# elysium_v0_7.net
KiCad netlist of a schematic drawn in EAGLE
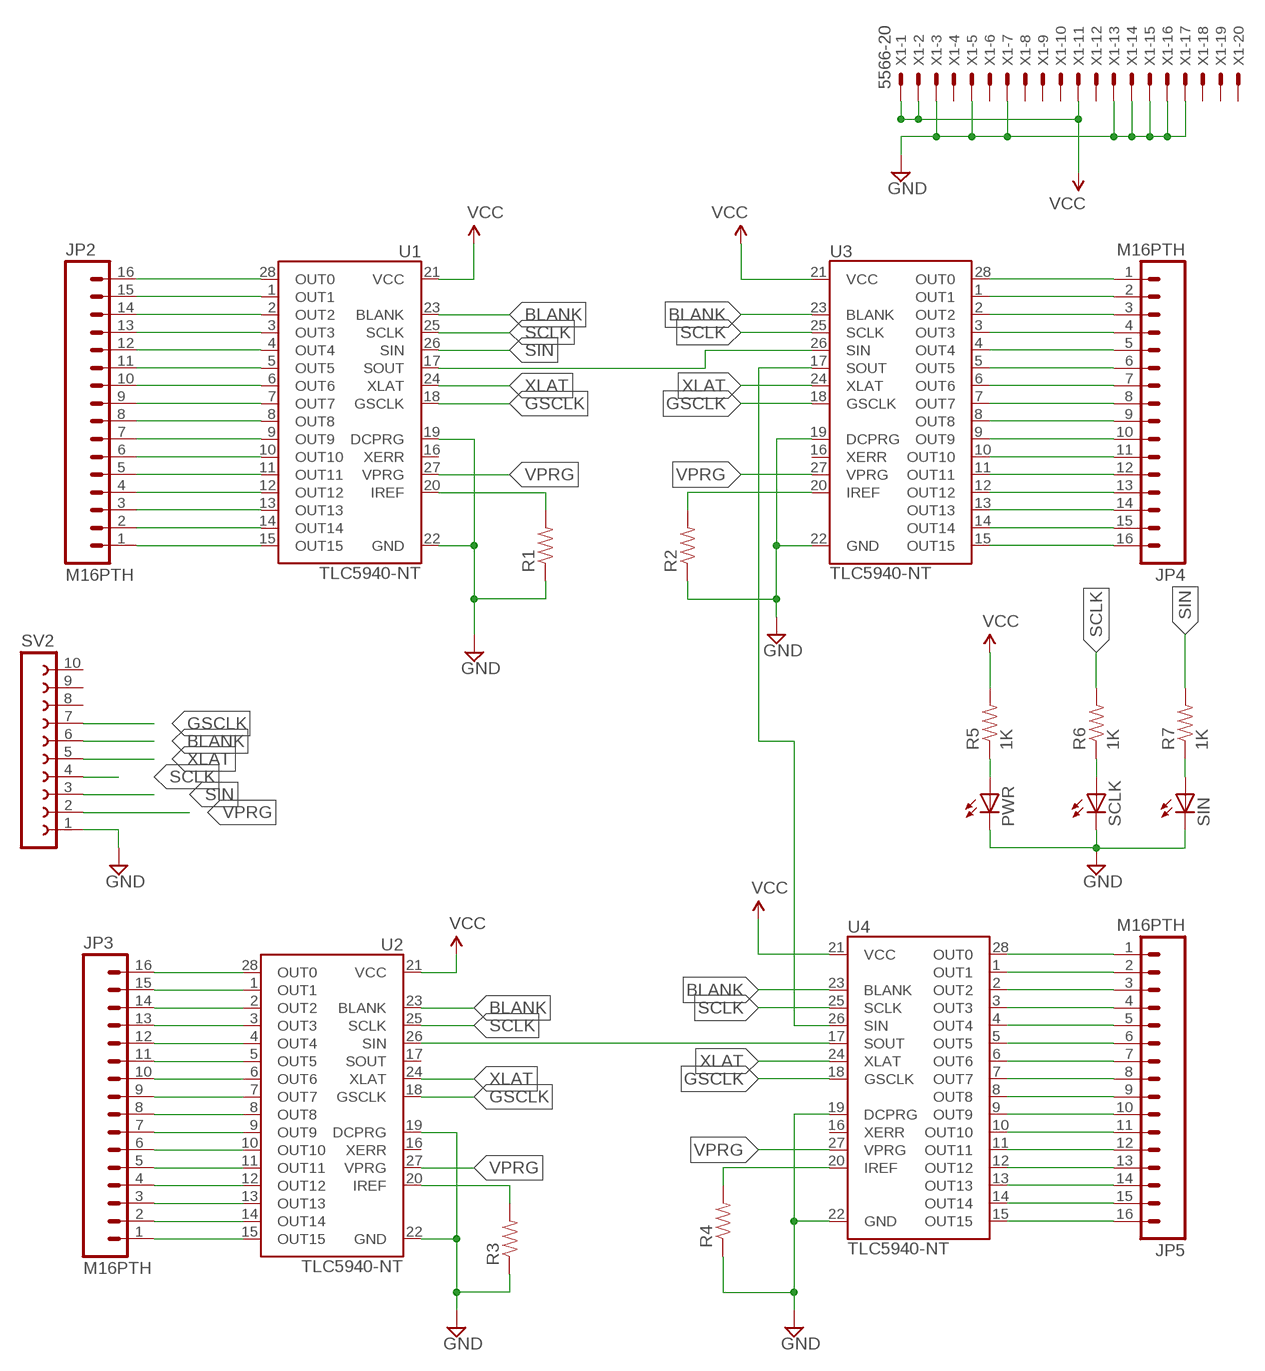
[diagram p0: schematic, sheet 1]

(export (version "E")
  (design (tool "Eeschema 10.0.6"))
  (components
    (comp (ref "JP2")
      (value "M16PTH")
      (footprint "eagle-import:1X16")
      (libsource (lib "eagle-import") (part "M16PTH"))
    )
    (comp (ref "JP3")
      (value "M16PTH")
      (footprint "eagle-import:1X16")
      (libsource (lib "eagle-import") (part "M16PTH"))
    )
    (comp (ref "JP4")
      (value "M16PTH")
      (footprint "eagle-import:1X16")
      (libsource (lib "eagle-import") (part "M16PTH"))
    )
    (comp (ref "JP5")
      (value "M16PTH")
      (footprint "eagle-import:1X16")
      (libsource (lib "eagle-import") (part "M16PTH"))
    )
    (comp (ref "PWR")
      (value "LED5MM")
      (footprint "eagle-import:LED5MM")
      (libsource (lib "eagle-import") (part "LED5MM"))
    )
    (comp (ref "R1")
      (value "RESISTOREZ")
      (footprint "eagle-import:AXIAL-0.3EZ")
      (libsource (lib "eagle-import") (part "RESISTOREZ"))
    )
    (comp (ref "R2")
      (value "RESISTOREZ")
      (footprint "eagle-import:AXIAL-0.3EZ")
      (libsource (lib "eagle-import") (part "RESISTOREZ"))
    )
    (comp (ref "R3")
      (value "RESISTOREZ")
      (footprint "eagle-import:AXIAL-0.3EZ")
      (libsource (lib "eagle-import") (part "RESISTOREZ"))
    )
    (comp (ref "R4")
      (value "RESISTOREZ")
      (footprint "eagle-import:AXIAL-0.3EZ")
      (libsource (lib "eagle-import") (part "RESISTOREZ"))
    )
    (comp (ref "R5")
      (value "1K")
      (footprint "eagle-import:AXIAL-0.3EZ")
      (libsource (lib "eagle-import") (part "RESISTOREZ"))
    )
    (comp (ref "R6")
      (value "1K")
      (footprint "eagle-import:AXIAL-0.3EZ")
      (libsource (lib "eagle-import") (part "RESISTOREZ"))
    )
    (comp (ref "R7")
      (value "1K")
      (footprint "eagle-import:AXIAL-0.3EZ")
      (libsource (lib "eagle-import") (part "RESISTOREZ"))
    )
    (comp (ref "SCLK")
      (value "LED5MM")
      (footprint "eagle-import:LED5MM")
      (libsource (lib "eagle-import") (part "LED5MM"))
    )
    (comp (ref "SIN")
      (value "LED5MM")
      (footprint "eagle-import:LED5MM")
      (libsource (lib "eagle-import") (part "LED5MM"))
    )
    (comp (ref "SV2")
      (value "FE10-1")
      (footprint "eagle-import:FE10")
      (libsource (lib "eagle-import") (part "FE10-1"))
    )
    (comp (ref "U1")
      (value "TLC5940-NT")
      (footprint "eagle-import:DIL28-3")
      (libsource (lib "eagle-import") (part "TLC5940-NT"))
    )
    (comp (ref "U2")
      (value "TLC5940-NT")
      (footprint "eagle-import:DIL28-3")
      (libsource (lib "eagle-import") (part "TLC5940-NT"))
    )
    (comp (ref "U3")
      (value "TLC5940-NT")
      (footprint "eagle-import:DIL28-3")
      (libsource (lib "eagle-import") (part "TLC5940-NT"))
    )
    (comp (ref "U4")
      (value "TLC5940-NT")
      (footprint "eagle-import:DIL28-3")
      (libsource (lib "eagle-import") (part "TLC5940-NT"))
    )
    (comp (ref "X1")
      (value "5566-20")
      (footprint "eagle-import:5566-20")
      (libsource (lib "eagle-import") (part "5566-20"))
    )
  )
  (nets
    (net (code "1") (name "BLANK") (class "Default")
      (node (ref "SV2") (pin "6") (pinfunction "6_6") (pintype "passive"))
      (node (ref "U1") (pin "23") (pinfunction "BLANK_23") (pintype "bidirectional"))
      (node (ref "U2") (pin "23") (pinfunction "BLANK_23") (pintype "bidirectional"))
      (node (ref "U3") (pin "23") (pinfunction "BLANK_23") (pintype "bidirectional"))
      (node (ref "U4") (pin "23") (pinfunction "BLANK_23") (pintype "bidirectional"))
    )
    (net (code "2") (name "GND") (class "Default")
      (node (ref "PWR") (pin "K") (pinfunction "C_K") (pintype "passive"))
      (node (ref "R1") (pin "P$1") (pinfunction "1_P$1") (pintype "passive"))
      (node (ref "R2") (pin "P$1") (pinfunction "1_P$1") (pintype "passive"))
      (node (ref "R3") (pin "P$1") (pinfunction "1_P$1") (pintype "passive"))
      (node (ref "R4") (pin "P$1") (pinfunction "1_P$1") (pintype "passive"))
      (node (ref "SCLK") (pin "K") (pinfunction "C_K") (pintype "passive"))
      (node (ref "SIN") (pin "K") (pinfunction "C_K") (pintype "passive"))
      (node (ref "SV2") (pin "1") (pinfunction "1_1") (pintype "passive"))
      (node (ref "U1") (pin "19") (pinfunction "DCPRG_19") (pintype "bidirectional"))
      (node (ref "U1") (pin "22") (pinfunction "GND_22") (pintype "bidirectional"))
      (node (ref "U2") (pin "19") (pinfunction "DCPRG_19") (pintype "bidirectional"))
      (node (ref "U2") (pin "22") (pinfunction "GND_22") (pintype "bidirectional"))
      (node (ref "U3") (pin "19") (pinfunction "DCPRG_19") (pintype "bidirectional"))
      (node (ref "U3") (pin "22") (pinfunction "GND_22") (pintype "bidirectional"))
      (node (ref "U4") (pin "19") (pinfunction "DCPRG_19") (pintype "bidirectional"))
      (node (ref "U4") (pin "22") (pinfunction "GND_22") (pintype "bidirectional"))
      (node (ref "X1") (pin "13") (pinfunction "S_13") (pintype "passive"))
      (node (ref "X1") (pin "14") (pinfunction "S_14") (pintype "passive"))
      (node (ref "X1") (pin "15") (pinfunction "S_15") (pintype "passive"))
      (node (ref "X1") (pin "16") (pinfunction "S_16") (pintype "passive"))
      (node (ref "X1") (pin "17") (pinfunction "S_17") (pintype "passive"))
      (node (ref "X1") (pin "3") (pinfunction "S_3") (pintype "passive"))
      (node (ref "X1") (pin "5") (pinfunction "S_5") (pintype "passive"))
      (node (ref "X1") (pin "7") (pinfunction "S_7") (pintype "passive"))
    )
    (net (code "3") (name "GSCLK") (class "Default")
      (node (ref "SV2") (pin "7") (pinfunction "7_7") (pintype "passive"))
      (node (ref "U1") (pin "18") (pinfunction "GSCLK_18") (pintype "bidirectional"))
      (node (ref "U2") (pin "18") (pinfunction "GSCLK_18") (pintype "bidirectional"))
      (node (ref "U3") (pin "18") (pinfunction "GSCLK_18") (pintype "bidirectional"))
      (node (ref "U4") (pin "18") (pinfunction "GSCLK_18") (pintype "bidirectional"))
    )
    (net (code "4") (name "Net-(R1-2)") (class "Default")
      (node (ref "R1") (pin "P$2") (pinfunction "2_P$2") (pintype "passive"))
      (node (ref "U1") (pin "20") (pinfunction "IREF_20") (pintype "bidirectional"))
    )
    (net (code "5") (name "Net-(R2-2)") (class "Default")
      (node (ref "R2") (pin "P$2") (pinfunction "2_P$2") (pintype "passive"))
      (node (ref "U3") (pin "20") (pinfunction "IREF_20") (pintype "bidirectional"))
    )
    (net (code "6") (name "Net-(R3-2)") (class "Default")
      (node (ref "R3") (pin "P$2") (pinfunction "2_P$2") (pintype "passive"))
      (node (ref "U2") (pin "20") (pinfunction "IREF_20") (pintype "bidirectional"))
    )
    (net (code "7") (name "Net-(R4-2)") (class "Default")
      (node (ref "R4") (pin "P$2") (pinfunction "2_P$2") (pintype "passive"))
      (node (ref "U4") (pin "20") (pinfunction "IREF_20") (pintype "bidirectional"))
    )
    (net (code "8") (name "Net-(R5-1)") (class "Default")
      (node (ref "PWR") (pin "A") (pinfunction "A_A") (pintype "passive"))
      (node (ref "R5") (pin "P$1") (pinfunction "1_P$1") (pintype "passive"))
    )
    (net (code "9") (name "Net-(R6-1)") (class "Default")
      (node (ref "R6") (pin "P$1") (pinfunction "1_P$1") (pintype "passive"))
      (node (ref "SCLK") (pin "A") (pinfunction "A_A") (pintype "passive"))
    )
    (net (code "10") (name "Net-(R7-1)") (class "Default")
      (node (ref "R7") (pin "P$1") (pinfunction "1_P$1") (pintype "passive"))
      (node (ref "SIN") (pin "A") (pinfunction "A_A") (pintype "passive"))
    )
    (net (code "11") (name "Net-(U1-OUT0)") (class "Default")
      (node (ref "JP2") (pin "16") (pinfunction "16_16") (pintype "passive"))
      (node (ref "U1") (pin "28") (pinfunction "OUT0_28") (pintype "bidirectional"))
    )
    (net (code "12") (name "Net-(U1-OUT1)") (class "Default")
      (node (ref "JP2") (pin "15") (pinfunction "15_15") (pintype "passive"))
      (node (ref "U1") (pin "1") (pinfunction "OUT1_1") (pintype "bidirectional"))
    )
    (net (code "13") (name "Net-(U1-OUT2)") (class "Default")
      (node (ref "JP2") (pin "14") (pinfunction "14_14") (pintype "passive"))
      (node (ref "U1") (pin "2") (pinfunction "OUT2_2") (pintype "bidirectional"))
    )
    (net (code "14") (name "Net-(U1-OUT3)") (class "Default")
      (node (ref "JP2") (pin "13") (pinfunction "13_13") (pintype "passive"))
      (node (ref "U1") (pin "3") (pinfunction "OUT3_3") (pintype "bidirectional"))
    )
    (net (code "15") (name "Net-(U1-OUT4)") (class "Default")
      (node (ref "JP2") (pin "12") (pinfunction "12_12") (pintype "passive"))
      (node (ref "U1") (pin "4") (pinfunction "OUT4_4") (pintype "bidirectional"))
    )
    (net (code "16") (name "Net-(U1-OUT5)") (class "Default")
      (node (ref "JP2") (pin "11") (pinfunction "11_11") (pintype "passive"))
      (node (ref "U1") (pin "5") (pinfunction "OUT5_5") (pintype "bidirectional"))
    )
    (net (code "17") (name "Net-(U1-OUT6)") (class "Default")
      (node (ref "JP2") (pin "10") (pinfunction "10_10") (pintype "passive"))
      (node (ref "U1") (pin "6") (pinfunction "OUT6_6") (pintype "bidirectional"))
    )
    (net (code "18") (name "Net-(U1-OUT7)") (class "Default")
      (node (ref "JP2") (pin "9") (pinfunction "9_9") (pintype "passive"))
      (node (ref "U1") (pin "7") (pinfunction "OUT7_7") (pintype "bidirectional"))
    )
    (net (code "19") (name "Net-(U1-OUT8)") (class "Default")
      (node (ref "JP2") (pin "8") (pinfunction "8_8") (pintype "passive"))
      (node (ref "U1") (pin "8") (pinfunction "OUT8_8") (pintype "bidirectional"))
    )
    (net (code "20") (name "Net-(U1-OUT9)") (class "Default")
      (node (ref "JP2") (pin "7") (pinfunction "7_7") (pintype "passive"))
      (node (ref "U1") (pin "9") (pinfunction "OUT9_9") (pintype "bidirectional"))
    )
    (net (code "21") (name "Net-(U1-OUT10)") (class "Default")
      (node (ref "JP2") (pin "6") (pinfunction "6_6") (pintype "passive"))
      (node (ref "U1") (pin "10") (pinfunction "OUT10_10") (pintype "bidirectional"))
    )
    (net (code "22") (name "Net-(U1-OUT11)") (class "Default")
      (node (ref "JP2") (pin "5") (pinfunction "5_5") (pintype "passive"))
      (node (ref "U1") (pin "11") (pinfunction "OUT11_11") (pintype "bidirectional"))
    )
    (net (code "23") (name "Net-(U1-OUT12)") (class "Default")
      (node (ref "JP2") (pin "4") (pinfunction "4_4") (pintype "passive"))
      (node (ref "U1") (pin "12") (pinfunction "OUT12_12") (pintype "bidirectional"))
    )
    (net (code "24") (name "Net-(U1-OUT13)") (class "Default")
      (node (ref "JP2") (pin "3") (pinfunction "3_3") (pintype "passive"))
      (node (ref "U1") (pin "13") (pinfunction "OUT13_13") (pintype "bidirectional"))
    )
    (net (code "25") (name "Net-(U1-OUT14)") (class "Default")
      (node (ref "JP2") (pin "2") (pinfunction "2_2") (pintype "passive"))
      (node (ref "U1") (pin "14") (pinfunction "OUT14_14") (pintype "bidirectional"))
    )
    (net (code "26") (name "Net-(U1-OUT15)") (class "Default")
      (node (ref "JP2") (pin "1") (pinfunction "1_1") (pintype "passive"))
      (node (ref "U1") (pin "15") (pinfunction "OUT15_15") (pintype "bidirectional"))
    )
    (net (code "27") (name "Net-(U1-SOUT)") (class "Default")
      (node (ref "U1") (pin "17") (pinfunction "SOUT_17") (pintype "bidirectional"))
      (node (ref "U3") (pin "26") (pinfunction "SIN_26") (pintype "bidirectional"))
    )
    (net (code "28") (name "Net-(U2-OUT0)") (class "Default")
      (node (ref "JP3") (pin "16") (pinfunction "16_16") (pintype "passive"))
      (node (ref "U2") (pin "28") (pinfunction "OUT0_28") (pintype "bidirectional"))
    )
    (net (code "29") (name "Net-(U2-OUT1)") (class "Default")
      (node (ref "JP3") (pin "15") (pinfunction "15_15") (pintype "passive"))
      (node (ref "U2") (pin "1") (pinfunction "OUT1_1") (pintype "bidirectional"))
    )
    (net (code "30") (name "Net-(U2-OUT2)") (class "Default")
      (node (ref "JP3") (pin "14") (pinfunction "14_14") (pintype "passive"))
      (node (ref "U2") (pin "2") (pinfunction "OUT2_2") (pintype "bidirectional"))
    )
    (net (code "31") (name "Net-(U2-OUT3)") (class "Default")
      (node (ref "JP3") (pin "13") (pinfunction "13_13") (pintype "passive"))
      (node (ref "U2") (pin "3") (pinfunction "OUT3_3") (pintype "bidirectional"))
    )
    (net (code "32") (name "Net-(U2-OUT4)") (class "Default")
      (node (ref "JP3") (pin "12") (pinfunction "12_12") (pintype "passive"))
      (node (ref "U2") (pin "4") (pinfunction "OUT4_4") (pintype "bidirectional"))
    )
    (net (code "33") (name "Net-(U2-OUT5)") (class "Default")
      (node (ref "JP3") (pin "11") (pinfunction "11_11") (pintype "passive"))
      (node (ref "U2") (pin "5") (pinfunction "OUT5_5") (pintype "bidirectional"))
    )
    (net (code "34") (name "Net-(U2-OUT6)") (class "Default")
      (node (ref "JP3") (pin "10") (pinfunction "10_10") (pintype "passive"))
      (node (ref "U2") (pin "6") (pinfunction "OUT6_6") (pintype "bidirectional"))
    )
    (net (code "35") (name "Net-(U2-OUT7)") (class "Default")
      (node (ref "JP3") (pin "9") (pinfunction "9_9") (pintype "passive"))
      (node (ref "U2") (pin "7") (pinfunction "OUT7_7") (pintype "bidirectional"))
    )
    (net (code "36") (name "Net-(U2-OUT8)") (class "Default")
      (node (ref "JP3") (pin "8") (pinfunction "8_8") (pintype "passive"))
      (node (ref "U2") (pin "8") (pinfunction "OUT8_8") (pintype "bidirectional"))
    )
    (net (code "37") (name "Net-(U2-OUT9)") (class "Default")
      (node (ref "JP3") (pin "7") (pinfunction "7_7") (pintype "passive"))
      (node (ref "U2") (pin "9") (pinfunction "OUT9_9") (pintype "bidirectional"))
    )
    (net (code "38") (name "Net-(U2-OUT10)") (class "Default")
      (node (ref "JP3") (pin "6") (pinfunction "6_6") (pintype "passive"))
      (node (ref "U2") (pin "10") (pinfunction "OUT10_10") (pintype "bidirectional"))
    )
    (net (code "39") (name "Net-(U2-OUT11)") (class "Default")
      (node (ref "JP3") (pin "5") (pinfunction "5_5") (pintype "passive"))
      (node (ref "U2") (pin "11") (pinfunction "OUT11_11") (pintype "bidirectional"))
    )
    (net (code "40") (name "Net-(U2-OUT12)") (class "Default")
      (node (ref "JP3") (pin "4") (pinfunction "4_4") (pintype "passive"))
      (node (ref "U2") (pin "12") (pinfunction "OUT12_12") (pintype "bidirectional"))
    )
    (net (code "41") (name "Net-(U2-OUT13)") (class "Default")
      (node (ref "JP3") (pin "3") (pinfunction "3_3") (pintype "passive"))
      (node (ref "U2") (pin "13") (pinfunction "OUT13_13") (pintype "bidirectional"))
    )
    (net (code "42") (name "Net-(U2-OUT14)") (class "Default")
      (node (ref "JP3") (pin "2") (pinfunction "2_2") (pintype "passive"))
      (node (ref "U2") (pin "14") (pinfunction "OUT14_14") (pintype "bidirectional"))
    )
    (net (code "43") (name "Net-(U2-OUT15)") (class "Default")
      (node (ref "JP3") (pin "1") (pinfunction "1_1") (pintype "passive"))
      (node (ref "U2") (pin "15") (pinfunction "OUT15_15") (pintype "bidirectional"))
    )
    (net (code "44") (name "Net-(U2-SIN)") (class "Default")
      (node (ref "U2") (pin "26") (pinfunction "SIN_26") (pintype "bidirectional"))
      (node (ref "U4") (pin "17") (pinfunction "SOUT_17") (pintype "bidirectional"))
    )
    (net (code "45") (name "Net-(U3-OUT0)") (class "Default")
      (node (ref "JP4") (pin "1") (pinfunction "1_1") (pintype "passive"))
      (node (ref "U3") (pin "28") (pinfunction "OUT0_28") (pintype "bidirectional"))
    )
    (net (code "46") (name "Net-(U3-OUT1)") (class "Default")
      (node (ref "JP4") (pin "2") (pinfunction "2_2") (pintype "passive"))
      (node (ref "U3") (pin "1") (pinfunction "OUT1_1") (pintype "bidirectional"))
    )
    (net (code "47") (name "Net-(U3-OUT2)") (class "Default")
      (node (ref "JP4") (pin "3") (pinfunction "3_3") (pintype "passive"))
      (node (ref "U3") (pin "2") (pinfunction "OUT2_2") (pintype "bidirectional"))
    )
    (net (code "48") (name "Net-(U3-OUT3)") (class "Default")
      (node (ref "JP4") (pin "4") (pinfunction "4_4") (pintype "passive"))
      (node (ref "U3") (pin "3") (pinfunction "OUT3_3") (pintype "bidirectional"))
    )
    (net (code "49") (name "Net-(U3-OUT4)") (class "Default")
      (node (ref "JP4") (pin "5") (pinfunction "5_5") (pintype "passive"))
      (node (ref "U3") (pin "4") (pinfunction "OUT4_4") (pintype "bidirectional"))
    )
    (net (code "50") (name "Net-(U3-OUT5)") (class "Default")
      (node (ref "JP4") (pin "6") (pinfunction "6_6") (pintype "passive"))
      (node (ref "U3") (pin "5") (pinfunction "OUT5_5") (pintype "bidirectional"))
    )
    (net (code "51") (name "Net-(U3-OUT6)") (class "Default")
      (node (ref "JP4") (pin "7") (pinfunction "7_7") (pintype "passive"))
      (node (ref "U3") (pin "6") (pinfunction "OUT6_6") (pintype "bidirectional"))
    )
    (net (code "52") (name "Net-(U3-OUT7)") (class "Default")
      (node (ref "JP4") (pin "8") (pinfunction "8_8") (pintype "passive"))
      (node (ref "U3") (pin "7") (pinfunction "OUT7_7") (pintype "bidirectional"))
    )
    (net (code "53") (name "Net-(U3-OUT8)") (class "Default")
      (node (ref "JP4") (pin "9") (pinfunction "9_9") (pintype "passive"))
      (node (ref "U3") (pin "8") (pinfunction "OUT8_8") (pintype "bidirectional"))
    )
    (net (code "54") (name "Net-(U3-OUT9)") (class "Default")
      (node (ref "JP4") (pin "10") (pinfunction "10_10") (pintype "passive"))
      (node (ref "U3") (pin "9") (pinfunction "OUT9_9") (pintype "bidirectional"))
    )
    (net (code "55") (name "Net-(U3-OUT10)") (class "Default")
      (node (ref "JP4") (pin "11") (pinfunction "11_11") (pintype "passive"))
      (node (ref "U3") (pin "10") (pinfunction "OUT10_10") (pintype "bidirectional"))
    )
    (net (code "56") (name "Net-(U3-OUT11)") (class "Default")
      (node (ref "JP4") (pin "12") (pinfunction "12_12") (pintype "passive"))
      (node (ref "U3") (pin "11") (pinfunction "OUT11_11") (pintype "bidirectional"))
    )
    (net (code "57") (name "Net-(U3-OUT12)") (class "Default")
      (node (ref "JP4") (pin "13") (pinfunction "13_13") (pintype "passive"))
      (node (ref "U3") (pin "12") (pinfunction "OUT12_12") (pintype "bidirectional"))
    )
    (net (code "58") (name "Net-(U3-OUT13)") (class "Default")
      (node (ref "JP4") (pin "14") (pinfunction "14_14") (pintype "passive"))
      (node (ref "U3") (pin "13") (pinfunction "OUT13_13") (pintype "bidirectional"))
    )
    (net (code "59") (name "Net-(U3-OUT14)") (class "Default")
      (node (ref "JP4") (pin "15") (pinfunction "15_15") (pintype "passive"))
      (node (ref "U3") (pin "14") (pinfunction "OUT14_14") (pintype "bidirectional"))
    )
    (net (code "60") (name "Net-(U3-OUT15)") (class "Default")
      (node (ref "JP4") (pin "16") (pinfunction "16_16") (pintype "passive"))
      (node (ref "U3") (pin "15") (pinfunction "OUT15_15") (pintype "bidirectional"))
    )
    (net (code "61") (name "Net-(U3-SOUT)") (class "Default")
      (node (ref "U3") (pin "17") (pinfunction "SOUT_17") (pintype "bidirectional"))
      (node (ref "U4") (pin "26") (pinfunction "SIN_26") (pintype "bidirectional"))
    )
    (net (code "62") (name "Net-(U4-OUT0)") (class "Default")
      (node (ref "JP5") (pin "1") (pinfunction "1_1") (pintype "passive"))
      (node (ref "U4") (pin "28") (pinfunction "OUT0_28") (pintype "bidirectional"))
    )
    (net (code "63") (name "Net-(U4-OUT1)") (class "Default")
      (node (ref "JP5") (pin "2") (pinfunction "2_2") (pintype "passive"))
      (node (ref "U4") (pin "1") (pinfunction "OUT1_1") (pintype "bidirectional"))
    )
    (net (code "64") (name "Net-(U4-OUT2)") (class "Default")
      (node (ref "JP5") (pin "3") (pinfunction "3_3") (pintype "passive"))
      (node (ref "U4") (pin "2") (pinfunction "OUT2_2") (pintype "bidirectional"))
    )
    (net (code "65") (name "Net-(U4-OUT3)") (class "Default")
      (node (ref "JP5") (pin "4") (pinfunction "4_4") (pintype "passive"))
      (node (ref "U4") (pin "3") (pinfunction "OUT3_3") (pintype "bidirectional"))
    )
    (net (code "66") (name "Net-(U4-OUT4)") (class "Default")
      (node (ref "JP5") (pin "5") (pinfunction "5_5") (pintype "passive"))
      (node (ref "U4") (pin "4") (pinfunction "OUT4_4") (pintype "bidirectional"))
    )
    (net (code "67") (name "Net-(U4-OUT5)") (class "Default")
      (node (ref "JP5") (pin "6") (pinfunction "6_6") (pintype "passive"))
      (node (ref "U4") (pin "5") (pinfunction "OUT5_5") (pintype "bidirectional"))
    )
    (net (code "68") (name "Net-(U4-OUT6)") (class "Default")
      (node (ref "JP5") (pin "7") (pinfunction "7_7") (pintype "passive"))
      (node (ref "U4") (pin "6") (pinfunction "OUT6_6") (pintype "bidirectional"))
    )
    (net (code "69") (name "Net-(U4-OUT7)") (class "Default")
      (node (ref "JP5") (pin "8") (pinfunction "8_8") (pintype "passive"))
      (node (ref "U4") (pin "7") (pinfunction "OUT7_7") (pintype "bidirectional"))
    )
    (net (code "70") (name "Net-(U4-OUT8)") (class "Default")
      (node (ref "JP5") (pin "9") (pinfunction "9_9") (pintype "passive"))
      (node (ref "U4") (pin "8") (pinfunction "OUT8_8") (pintype "bidirectional"))
    )
    (net (code "71") (name "Net-(U4-OUT9)") (class "Default")
      (node (ref "JP5") (pin "10") (pinfunction "10_10") (pintype "passive"))
      (node (ref "U4") (pin "9") (pinfunction "OUT9_9") (pintype "bidirectional"))
    )
    (net (code "72") (name "Net-(U4-OUT10)") (class "Default")
      (node (ref "JP5") (pin "11") (pinfunction "11_11") (pintype "passive"))
      (node (ref "U4") (pin "10") (pinfunction "OUT10_10") (pintype "bidirectional"))
    )
    (net (code "73") (name "Net-(U4-OUT11)") (class "Default")
      (node (ref "JP5") (pin "12") (pinfunction "12_12") (pintype "passive"))
      (node (ref "U4") (pin "11") (pinfunction "OUT11_11") (pintype "bidirectional"))
    )
    (net (code "74") (name "Net-(U4-OUT12)") (class "Default")
      (node (ref "JP5") (pin "13") (pinfunction "13_13") (pintype "passive"))
      (node (ref "U4") (pin "12") (pinfunction "OUT12_12") (pintype "bidirectional"))
    )
    (net (code "75") (name "Net-(U4-OUT13)") (class "Default")
      (node (ref "JP5") (pin "14") (pinfunction "14_14") (pintype "passive"))
      (node (ref "U4") (pin "13") (pinfunction "OUT13_13") (pintype "bidirectional"))
    )
    (net (code "76") (name "Net-(U4-OUT14)") (class "Default")
      (node (ref "JP5") (pin "15") (pinfunction "15_15") (pintype "passive"))
      (node (ref "U4") (pin "14") (pinfunction "OUT14_14") (pintype "bidirectional"))
    )
    (net (code "77") (name "Net-(U4-OUT15)") (class "Default")
      (node (ref "JP5") (pin "16") (pinfunction "16_16") (pintype "passive"))
      (node (ref "U4") (pin "15") (pinfunction "OUT15_15") (pintype "bidirectional"))
    )
    (net (code "78") (name "SCLK") (class "Default")
      (node (ref "R6") (pin "P$2") (pinfunction "2_P$2") (pintype "passive"))
      (node (ref "SV2") (pin "4") (pinfunction "4_4") (pintype "passive"))
      (node (ref "U1") (pin "25") (pinfunction "SCLK_25") (pintype "bidirectional"))
      (node (ref "U2") (pin "25") (pinfunction "SCLK_25") (pintype "bidirectional"))
      (node (ref "U3") (pin "25") (pinfunction "SCLK_25") (pintype "bidirectional"))
      (node (ref "U4") (pin "25") (pinfunction "SCLK_25") (pintype "bidirectional"))
    )
    (net (code "79") (name "SIN") (class "Default")
      (node (ref "R7") (pin "P$2") (pinfunction "2_P$2") (pintype "passive"))
      (node (ref "SV2") (pin "3") (pinfunction "3_3") (pintype "passive"))
      (node (ref "U1") (pin "26") (pinfunction "SIN_26") (pintype "bidirectional"))
    )
    (net (code "80") (name "VCC") (class "Default")
      (node (ref "R5") (pin "P$2") (pinfunction "2_P$2") (pintype "passive"))
      (node (ref "U1") (pin "21") (pinfunction "VCC_21") (pintype "bidirectional"))
      (node (ref "U2") (pin "21") (pinfunction "VCC_21") (pintype "bidirectional"))
      (node (ref "U3") (pin "21") (pinfunction "VCC_21") (pintype "bidirectional"))
      (node (ref "U4") (pin "21") (pinfunction "VCC_21") (pintype "bidirectional"))
      (node (ref "X1") (pin "1") (pinfunction "S_1") (pintype "passive"))
      (node (ref "X1") (pin "11") (pinfunction "S_11") (pintype "passive"))
      (node (ref "X1") (pin "2") (pinfunction "S_2") (pintype "passive"))
    )
    (net (code "81") (name "VPRG") (class "Default")
      (node (ref "SV2") (pin "2") (pinfunction "2_2") (pintype "passive"))
      (node (ref "U1") (pin "27") (pinfunction "VPRG_27") (pintype "bidirectional"))
      (node (ref "U2") (pin "27") (pinfunction "VPRG_27") (pintype "bidirectional"))
      (node (ref "U3") (pin "27") (pinfunction "VPRG_27") (pintype "bidirectional"))
      (node (ref "U4") (pin "27") (pinfunction "VPRG_27") (pintype "bidirectional"))
    )
    (net (code "82") (name "XLAT") (class "Default")
      (node (ref "SV2") (pin "5") (pinfunction "5_5") (pintype "passive"))
      (node (ref "U1") (pin "24") (pinfunction "XLAT_24") (pintype "bidirectional"))
      (node (ref "U2") (pin "24") (pinfunction "XLAT_24") (pintype "bidirectional"))
      (node (ref "U3") (pin "24") (pinfunction "XLAT_24") (pintype "bidirectional"))
      (node (ref "U4") (pin "24") (pinfunction "XLAT_24") (pintype "bidirectional"))
    )
    (net (code "83") (name "unconnected-(SV2-Pad8)") (class "Default")
      (node (ref "SV2") (pin "8") (pinfunction "8_8") (pintype "passive"))
    )
    (net (code "84") (name "unconnected-(SV2-Pad9)") (class "Default")
      (node (ref "SV2") (pin "9") (pinfunction "9_9") (pintype "passive"))
    )
    (net (code "85") (name "unconnected-(SV2-Pad10)") (class "Default")
      (node (ref "SV2") (pin "10") (pinfunction "10_10") (pintype "passive"))
    )
    (net (code "86") (name "unconnected-(U1-XERR-Pad16)") (class "Default")
      (node (ref "U1") (pin "16") (pinfunction "XERR_16") (pintype "bidirectional"))
    )
    (net (code "87") (name "unconnected-(U2-SOUT-Pad17)") (class "Default")
      (node (ref "U2") (pin "17") (pinfunction "SOUT_17") (pintype "bidirectional"))
    )
    (net (code "88") (name "unconnected-(U2-XERR-Pad16)") (class "Default")
      (node (ref "U2") (pin "16") (pinfunction "XERR_16") (pintype "bidirectional"))
    )
    (net (code "89") (name "unconnected-(U3-XERR-Pad16)") (class "Default")
      (node (ref "U3") (pin "16") (pinfunction "XERR_16") (pintype "bidirectional"))
    )
    (net (code "90") (name "unconnected-(U4-XERR-Pad16)") (class "Default")
      (node (ref "U4") (pin "16") (pinfunction "XERR_16") (pintype "bidirectional"))
    )
    (net (code "91") (name "unconnected-(X1B-S-Pad10)") (class "Default")
      (node (ref "X1") (pin "10") (pinfunction "S_10") (pintype "passive"))
    )
    (net (code "92") (name "unconnected-(X1D-S-Pad12)") (class "Default")
      (node (ref "X1") (pin "12") (pinfunction "S_12") (pintype "passive"))
    )
    (net (code "93") (name "unconnected-(X1J-S-Pad18)") (class "Default")
      (node (ref "X1") (pin "18") (pinfunction "S_18") (pintype "passive"))
    )
    (net (code "94") (name "unconnected-(X1K-S-Pad19)") (class "Default")
      (node (ref "X1") (pin "19") (pinfunction "S_19") (pintype "passive"))
    )
    (net (code "95") (name "unconnected-(X1M-S-Pad20)") (class "Default")
      (node (ref "X1") (pin "20") (pinfunction "S_20") (pintype "passive"))
    )
    (net (code "96") (name "unconnected-(X1O-S-Pad4)") (class "Default")
      (node (ref "X1") (pin "4") (pinfunction "S_4") (pintype "passive"))
    )
    (net (code "97") (name "unconnected-(X1Q-S-Pad6)") (class "Default")
      (node (ref "X1") (pin "6") (pinfunction "S_6") (pintype "passive"))
    )
    (net (code "98") (name "unconnected-(X1S-S-Pad8)") (class "Default")
      (node (ref "X1") (pin "8") (pinfunction "S_8") (pintype "passive"))
    )
    (net (code "99") (name "unconnected-(X1T-S-Pad9)") (class "Default")
      (node (ref "X1") (pin "9") (pinfunction "S_9") (pintype "passive"))
    )
  )
)
